# MAGI_sBuckPower.net
KiCad netlist of a schematic drawn in Altium Designer
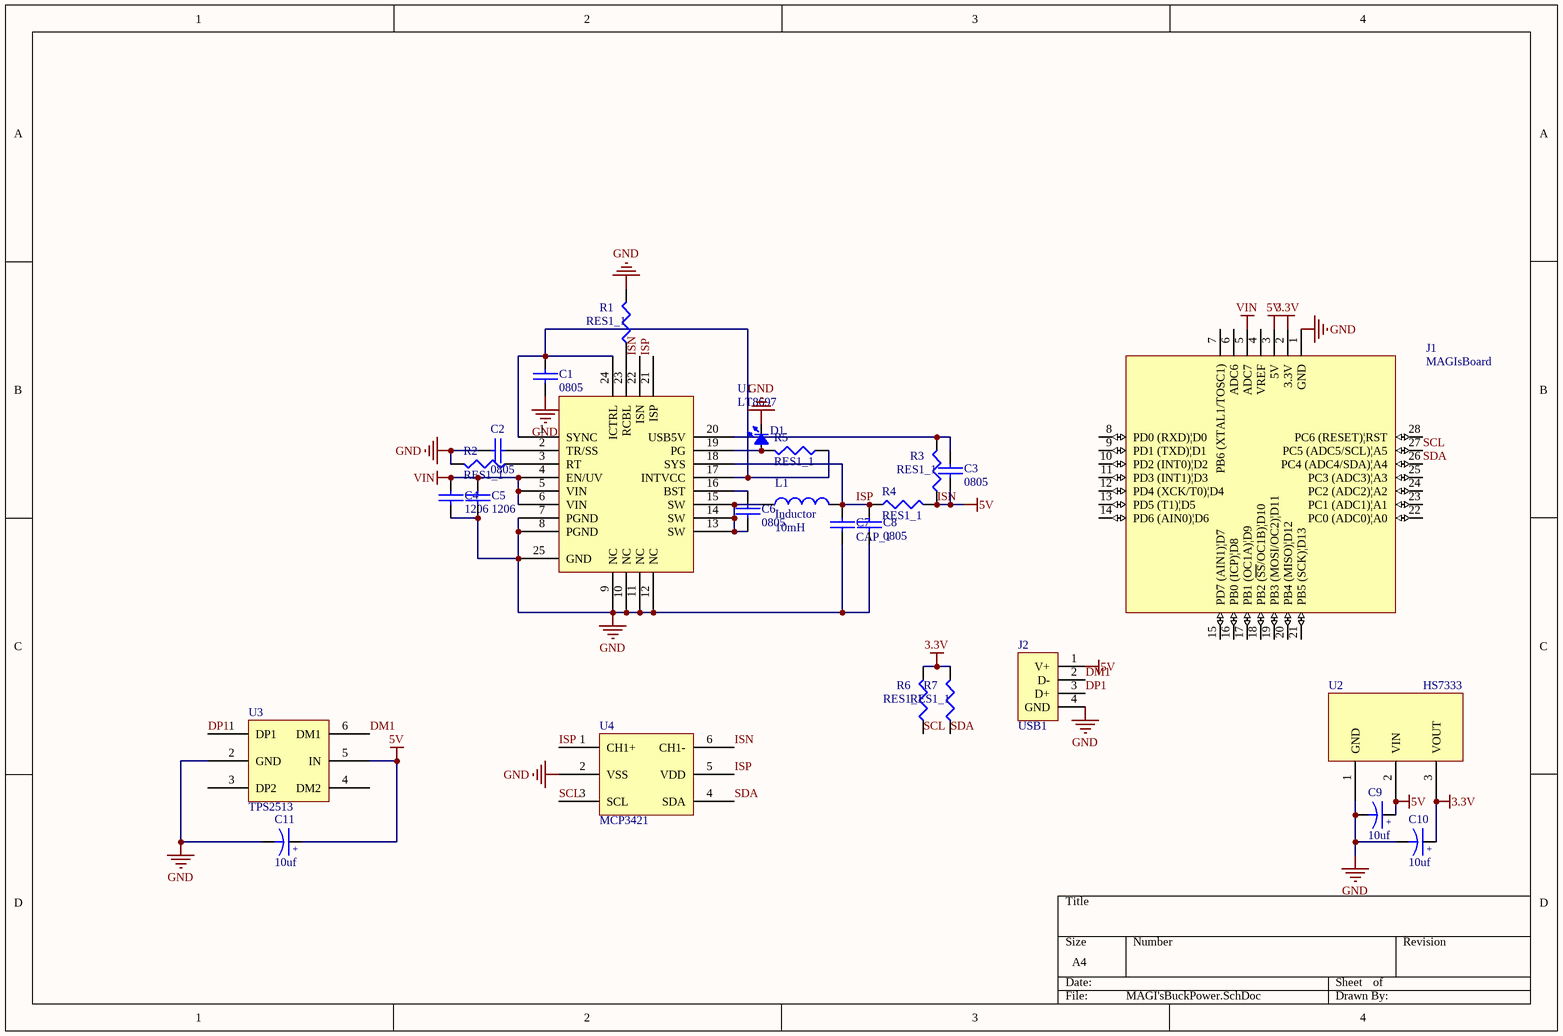
[diagram p0: MAGI'sBuckPower.SchDoc]

(export (version "E")
  (design (tool "Eeschema 10.0.6"))
  (components
    (comp (ref "C1")
      (value "0805")
      (footprint "6-0805_N")
      (description "Capacitor")
      (libsource (lib "电容器") (part "CAP_1"))
    )
    (comp (ref "C2")
      (value "0805")
      (footprint "6-0805_N")
      (description "Capacitor")
      (libsource (lib "电容器") (part "CAP_1"))
    )
    (comp (ref "C3")
      (value "0805")
      (footprint "6-0805_N")
      (description "Capacitor")
      (libsource (lib "电容器") (part "CAP_1"))
    )
    (comp (ref "C4")
      (value "1206")
      (footprint "C1206")
      (description "Capacitor")
      (libsource (lib "电容器") (part "CAP_1"))
    )
    (comp (ref "C5")
      (value "1206")
      (footprint "C1206")
      (description "Capacitor")
      (libsource (lib "电容器") (part "CAP_1"))
    )
    (comp (ref "C6")
      (value "0805")
      (footprint "6-0805_N")
      (description "Capacitor")
      (libsource (lib "电容器") (part "CAP_1"))
    )
    (comp (ref "C7")
      (value "CAP_1")
      (footprint "6TPE330M")
      (description "Capacitor")
      (libsource (lib "电容器") (part "CAP_1"))
    )
    (comp (ref "C8")
      (value "0805")
      (footprint "C1210_N")
      (description "Capacitor")
      (libsource (lib "电容器") (part "CAP_1"))
    )
    (comp (ref "C9")
      (value "10uf")
      (footprint "6-0805_n")
      (description "Capacitor")
      (libsource (lib "电容器") (part "CAPACITOR POL"))
    )
    (comp (ref "C10")
      (value "10uf")
      (footprint "6-0805_n")
      (description "Capacitor")
      (libsource (lib "电容器") (part "CAPACITOR POL"))
    )
    (comp (ref "C11")
      (value "10uf")
      (footprint "6-0805_N")
      (description "Capacitor")
      (libsource (lib "电容器") (part "CAPACITOR POL"))
    )
    (comp (ref "D1")
      (value "LED_0805")
      (footprint "6-0805_n")
      (description "LED")
      (libsource (lib "SCH_Active") (part "LED_0805"))
    )
    (comp (ref "J1")
      (value "MAGIsBoard")
      (footprint "MAGIsBoard")
      (libsource (lib "MAGIsBoard") (part "MAGIsBoard"))
    )
    (comp (ref "J2") (value "USB1") (footprint "USB-04A") (libsource (lib "USB接口") (part "USB1")))
    (comp (ref "L1")
      (value "Inductor")
      (footprint "7*7")
      (fields (field (name "ALTIUM_VALUE") "10mH") (field (name "PUBLISHER") "Altium Limited"))
      (libsource (lib "Miscellaneous Devices") (part "Inductor"))
    )
    (comp (ref "R1") (value "RES1_1") (footprint "6-0805_n") (libsource (lib "电阻器") (part "RES1_1")))
    (comp (ref "R2") (value "RES1_1") (footprint "6-0805_n") (libsource (lib "电阻器") (part "RES1_1")))
    (comp (ref "R3") (value "RES1_1") (footprint "6-0805_n") (libsource (lib "电阻器") (part "RES1_1")))
    (comp (ref "R4") (value "RES1_1") (footprint "2512") (libsource (lib "电阻器") (part "RES1_1")))
    (comp (ref "R5") (value "RES1_1") (footprint "6-0805_n") (libsource (lib "电阻器") (part "RES1_1")))
    (comp (ref "R6") (value "RES1_1") (footprint "6-0805_n") (libsource (lib "电阻器") (part "RES1_1")))
    (comp (ref "R7") (value "RES1_1") (footprint "6-0805_n") (libsource (lib "电阻器") (part "RES1_1")))
    (comp (ref "U1") (value "LT8697") (footprint "lt8697") (libsource (lib "PMIC") (part "LT8697")))
    (comp (ref "U2") (value "HS7333") (footprint "HS7333") (libsource (lib "PMIC") (part "HS7333")))
    (comp (ref "U3") (value "TPS2513") (footprint "TPS2513") (libsource (lib "PMIC") (part "TPS2513")))
    (comp (ref "U4") (value "MCP3421") (footprint "tps2513") (libsource (lib "ADC") (part "MCP3421")))
  )
  (nets
    (net (code "1") (name "/DM1") (class "Default")
      (node (ref "J2") (pin "2") (pinfunction "D-_2") (pintype "passive"))
      (node (ref "U3") (pin "6") (pinfunction "DM1_6") (pintype "passive"))
    )
    (net (code "2") (name "/DP1") (class "Default")
      (node (ref "J2") (pin "3") (pinfunction "D+_3") (pintype "passive"))
      (node (ref "U3") (pin "1") (pinfunction "DP1_1") (pintype "passive"))
    )
    (net (code "3") (name "/ISP") (class "Default")
      (node (ref "C7") (pin "1") (pinfunction "1_1") (pintype "passive"))
      (node (ref "C8") (pin "1") (pinfunction "1_1") (pintype "passive"))
      (node (ref "L1") (pin "2") (pinfunction "2_2") (pintype "passive"))
      (node (ref "R4") (pin "1") (pinfunction "1_1") (pintype "passive"))
      (node (ref "U1") (pin "18") (pinfunction "SYS_18") (pintype "passive"))
      (node (ref "U1") (pin "21") (pinfunction "ISP_21") (pintype "passive"))
      (node (ref "U4") (pin "1") (pinfunction "CH1+_1") (pintype "passive"))
      (node (ref "U4") (pin "5") (pinfunction "VDD_5") (pintype "passive"))
    )
    (net (code "4") (name "/SCL") (class "Default")
      (node (ref "J1") (pin "27") (pinfunction "PC5_(ADC5/SCL)¦A5_27") (pintype "bidirectional"))
      (node (ref "R6") (pin "1") (pinfunction "1_1") (pintype "passive"))
      (node (ref "U4") (pin "3") (pinfunction "SCL_3") (pintype "passive"))
    )
    (net (code "5") (name "/SDA") (class "Default")
      (node (ref "J1") (pin "26") (pinfunction "PC4_(ADC4/SDA)¦A4_26") (pintype "bidirectional"))
      (node (ref "R7") (pin "1") (pinfunction "1_1") (pintype "passive"))
      (node (ref "U4") (pin "4") (pinfunction "SDA_4") (pintype "passive"))
    )
    (net (code "6") (name "3.3V") (class "Default")
      (node (ref "C10") (pin "1") (pinfunction "1_1") (pintype "passive"))
      (node (ref "J1") (pin "2") (pinfunction "3.3V_2") (pintype "power_in"))
      (node (ref "R6") (pin "2") (pinfunction "2_2") (pintype "passive"))
      (node (ref "R7") (pin "2") (pinfunction "2_2") (pintype "passive"))
      (node (ref "U2") (pin "3") (pinfunction "VOUT_3") (pintype "passive"))
    )
    (net (code "7") (name "5V") (class "Default")
      (node (ref "C11") (pin "1") (pinfunction "1_1") (pintype "passive"))
      (node (ref "C3") (pin "1") (pinfunction "1_1") (pintype "passive"))
      (node (ref "C9") (pin "1") (pinfunction "1_1") (pintype "passive"))
      (node (ref "J1") (pin "3") (pinfunction "5V_3") (pintype "power_in"))
      (node (ref "J2") (pin "1") (pinfunction "V+_1") (pintype "passive"))
      (node (ref "R3") (pin "1") (pinfunction "1_1") (pintype "passive"))
      (node (ref "R4") (pin "2") (pinfunction "2_2") (pintype "passive"))
      (node (ref "U1") (pin "22") (pinfunction "ISN_22") (pintype "passive"))
      (node (ref "U2") (pin "2") (pinfunction "VIN_2") (pintype "passive"))
      (node (ref "U3") (pin "5") (pinfunction "IN_5") (pintype "passive"))
      (node (ref "U4") (pin "6") (pinfunction "CH1-_6") (pintype "passive"))
    )
    (net (code "8") (name "GND") (class "Default")
      (node (ref "C1") (pin "1") (pinfunction "1_1") (pintype "passive"))
      (node (ref "C10") (pin "2") (pinfunction "2_2") (pintype "passive"))
      (node (ref "C11") (pin "2") (pinfunction "2_2") (pintype "passive"))
      (node (ref "C2") (pin "2") (pinfunction "2_2") (pintype "passive"))
      (node (ref "C4") (pin "1") (pinfunction "1_1") (pintype "passive"))
      (node (ref "C5") (pin "1") (pinfunction "1_1") (pintype "passive"))
      (node (ref "C7") (pin "2") (pinfunction "2_2") (pintype "passive"))
      (node (ref "C8") (pin "2") (pinfunction "2_2") (pintype "passive"))
      (node (ref "C9") (pin "2") (pinfunction "2_2") (pintype "passive"))
      (node (ref "D1") (pin "2") (pinfunction "K_2") (pintype "passive"))
      (node (ref "J1") (pin "1") (pinfunction "GND_1") (pintype "power_in"))
      (node (ref "J2") (pin "4") (pinfunction "GND_4") (pintype "passive"))
      (node (ref "R1") (pin "2") (pinfunction "2_2") (pintype "passive"))
      (node (ref "R2") (pin "2") (pinfunction "2_2") (pintype "passive"))
      (node (ref "U1") (pin "10") (pinfunction "NC_10") (pintype "passive"))
      (node (ref "U1") (pin "11") (pinfunction "NC_11") (pintype "passive"))
      (node (ref "U1") (pin "12") (pinfunction "NC_12") (pintype "passive"))
      (node (ref "U1") (pin "25") (pinfunction "GND_25") (pintype "passive"))
      (node (ref "U1") (pin "7") (pinfunction "PGND_7") (pintype "passive"))
      (node (ref "U1") (pin "8") (pinfunction "PGND_8") (pintype "passive"))
      (node (ref "U1") (pin "9") (pinfunction "NC_9") (pintype "passive"))
      (node (ref "U2") (pin "1") (pinfunction "GND_1") (pintype "passive"))
      (node (ref "U3") (pin "2") (pinfunction "GND_2") (pintype "passive"))
      (node (ref "U4") (pin "2") (pinfunction "VSS_2") (pintype "passive"))
    )
    (net (code "9") (name "Net-(C6-Pad1)") (class "Default")
      (node (ref "C6") (pin "1") (pinfunction "1_1") (pintype "passive"))
      (node (ref "L1") (pin "1") (pinfunction "1_1") (pintype "passive"))
      (node (ref "U1") (pin "13") (pinfunction "SW_13") (pintype "passive"))
      (node (ref "U1") (pin "14") (pinfunction "SW_14") (pintype "passive"))
      (node (ref "U1") (pin "15") (pinfunction "SW_15") (pintype "passive"))
    )
    (net (code "10") (name "Net-(D1-A)") (class "Default")
      (node (ref "D1") (pin "1") (pinfunction "A_1") (pintype "passive"))
      (node (ref "R5") (pin "2") (pinfunction "2_2") (pintype "passive"))
      (node (ref "U1") (pin "19") (pinfunction "PG_19") (pintype "passive"))
    )
    (net (code "11") (name "Net-(U1-BST)") (class "Default")
      (node (ref "C6") (pin "2") (pinfunction "2_2") (pintype "passive"))
      (node (ref "U1") (pin "16") (pinfunction "BST_16") (pintype "passive"))
    )
    (net (code "12") (name "Net-(U1-ICTRL)") (class "Default")
      (node (ref "C1") (pin "2") (pinfunction "2_2") (pintype "passive"))
      (node (ref "R5") (pin "1") (pinfunction "1_1") (pintype "passive"))
      (node (ref "U1") (pin "1") (pinfunction "SYNC_1") (pintype "passive"))
      (node (ref "U1") (pin "17") (pinfunction "INTVCC_17") (pintype "passive"))
      (node (ref "U1") (pin "24") (pinfunction "ICTRL_24") (pintype "passive"))
    )
    (net (code "13") (name "Net-(U1-RCBL)") (class "Default")
      (node (ref "R1") (pin "1") (pinfunction "1_1") (pintype "passive"))
      (node (ref "U1") (pin "23") (pinfunction "RCBL_23") (pintype "passive"))
    )
    (net (code "14") (name "Net-(U1-RT)") (class "Default")
      (node (ref "R2") (pin "1") (pinfunction "1_1") (pintype "passive"))
      (node (ref "U1") (pin "3") (pinfunction "RT_3") (pintype "passive"))
    )
    (net (code "15") (name "Net-(U1-TR{slash}SS)") (class "Default")
      (node (ref "C2") (pin "1") (pinfunction "1_1") (pintype "passive"))
      (node (ref "U1") (pin "2") (pinfunction "TR/SS_2") (pintype "passive"))
    )
    (net (code "16") (name "Net-(U1-USB5V)") (class "Default")
      (node (ref "C3") (pin "2") (pinfunction "2_2") (pintype "passive"))
      (node (ref "R3") (pin "2") (pinfunction "2_2") (pintype "passive"))
      (node (ref "U1") (pin "20") (pinfunction "USB5V_20") (pintype "passive"))
    )
    (net (code "17") (name "VIN") (class "Default")
      (node (ref "C4") (pin "2") (pinfunction "2_2") (pintype "passive"))
      (node (ref "C5") (pin "2") (pinfunction "2_2") (pintype "passive"))
      (node (ref "J1") (pin "5") (pinfunction "ADC7_5") (pintype "passive"))
      (node (ref "U1") (pin "4") (pinfunction "EN/UV_4") (pintype "passive"))
      (node (ref "U1") (pin "5") (pinfunction "VIN_5") (pintype "passive"))
      (node (ref "U1") (pin "6") (pinfunction "VIN_6") (pintype "passive"))
    )
    (net (code "18") (name "unconnected-(J1-ADC6-Pad6)") (class "Default")
      (node (ref "J1") (pin "6") (pinfunction "ADC6_6") (pintype "passive"))
    )
    (net (code "19") (name "unconnected-(J1-PB0_(ICP)¦D8-Pad16)") (class "Default")
      (node (ref "J1") (pin "16") (pinfunction "PB0_(ICP)¦D8_16") (pintype "bidirectional"))
    )
    (net (code "20") (name "unconnected-(J1-PB1_(OC1A)¦D9-Pad17)") (class "Default")
      (node (ref "J1") (pin "17") (pinfunction "PB1_(OC1A)¦D9_17") (pintype "bidirectional"))
    )
    (net (code "21") (name "unconnected-(J1-PB2_(~{SS}{slash}OC1B)¦D10-Pad18)") (class "Default")
      (node (ref "J1") (pin "18") (pinfunction "PB2_(~{SS}/OC1B)¦D10_18") (pintype "bidirectional"))
    )
    (net (code "22") (name "unconnected-(J1-PB3_(MOSI{slash}OC2)¦D11-Pad19)") (class "Default")
      (node (ref "J1") (pin "19") (pinfunction "PB3_(MOSI/OC2)¦D11_19") (pintype "bidirectional"))
    )
    (net (code "23") (name "unconnected-(J1-PB4_(MISO)¦D12-Pad20)") (class "Default")
      (node (ref "J1") (pin "20") (pinfunction "PB4_(MISO)¦D12_20") (pintype "bidirectional"))
    )
    (net (code "24") (name "unconnected-(J1-PB5_(SCK)¦D13-Pad21)") (class "Default")
      (node (ref "J1") (pin "21") (pinfunction "PB5_(SCK)¦D13_21") (pintype "bidirectional"))
    )
    (net (code "25") (name "unconnected-(J1-PB6_(XTAL1{slash}TOSC1)-Pad7)") (class "Default")
      (node (ref "J1") (pin "7") (pinfunction "PB6_(XTAL1/TOSC1)_7") (pintype "passive"))
    )
    (net (code "26") (name "unconnected-(J1-PC0_(ADC0)¦A0-Pad22)") (class "Default")
      (node (ref "J1") (pin "22") (pinfunction "PC0_(ADC0)¦A0_22") (pintype "bidirectional"))
    )
    (net (code "27") (name "unconnected-(J1-PC1_(ADC1)¦A1-Pad23)") (class "Default")
      (node (ref "J1") (pin "23") (pinfunction "PC1_(ADC1)¦A1_23") (pintype "bidirectional"))
    )
    (net (code "28") (name "unconnected-(J1-PC2_(ADC2)¦A2-Pad24)") (class "Default")
      (node (ref "J1") (pin "24") (pinfunction "PC2_(ADC2)¦A2_24") (pintype "bidirectional"))
    )
    (net (code "29") (name "unconnected-(J1-PC3_(ADC3)¦A3-Pad25)") (class "Default")
      (node (ref "J1") (pin "25") (pinfunction "PC3_(ADC3)¦A3_25") (pintype "bidirectional"))
    )
    (net (code "30") (name "unconnected-(J1-PC6_(RESET)¦RST-Pad28)") (class "Default")
      (node (ref "J1") (pin "28") (pinfunction "PC6_(RESET)¦RST_28") (pintype "bidirectional"))
    )
    (net (code "31") (name "unconnected-(J1-PD0_(RXD)¦D0-Pad8)") (class "Default")
      (node (ref "J1") (pin "8") (pinfunction "PD0_(RXD)¦D0_8") (pintype "bidirectional"))
    )
    (net (code "32") (name "unconnected-(J1-PD1_(TXD)¦D1-Pad9)") (class "Default")
      (node (ref "J1") (pin "9") (pinfunction "PD1_(TXD)¦D1_9") (pintype "bidirectional"))
    )
    (net (code "33") (name "unconnected-(J1-PD2_(INT0)¦D2-Pad10)") (class "Default")
      (node (ref "J1") (pin "10") (pinfunction "PD2_(INT0)¦D2_10") (pintype "bidirectional"))
    )
    (net (code "34") (name "unconnected-(J1-PD3_(INT1)¦D3-Pad11)") (class "Default")
      (node (ref "J1") (pin "11") (pinfunction "PD3_(INT1)¦D3_11") (pintype "bidirectional"))
    )
    (net (code "35") (name "unconnected-(J1-PD4_(XCK{slash}T0)¦D4-Pad12)") (class "Default")
      (node (ref "J1") (pin "12") (pinfunction "PD4_(XCK/T0)¦D4_12") (pintype "bidirectional"))
    )
    (net (code "36") (name "unconnected-(J1-PD5_(T1)¦D5-Pad13)") (class "Default")
      (node (ref "J1") (pin "13") (pinfunction "PD5_(T1)¦D5_13") (pintype "bidirectional"))
    )
    (net (code "37") (name "unconnected-(J1-PD6_(AIN0)¦D6-Pad14)") (class "Default")
      (node (ref "J1") (pin "14") (pinfunction "PD6_(AIN0)¦D6_14") (pintype "bidirectional"))
    )
    (net (code "38") (name "unconnected-(J1-PD7_(AIN1)¦D7-Pad15)") (class "Default")
      (node (ref "J1") (pin "15") (pinfunction "PD7_(AIN1)¦D7_15") (pintype "bidirectional"))
    )
    (net (code "39") (name "unconnected-(J1-VREF-Pad4)") (class "Default")
      (node (ref "J1") (pin "4") (pinfunction "VREF_4") (pintype "passive"))
    )
    (net (code "40") (name "unconnected-(U3-DM2-Pad4)") (class "Default")
      (node (ref "U3") (pin "4") (pinfunction "DM2_4") (pintype "passive"))
    )
    (net (code "41") (name "unconnected-(U3-DP2-Pad3)") (class "Default")
      (node (ref "U3") (pin "3") (pinfunction "DP2_3") (pintype "passive"))
    )
  )
)
